# led-cc-driver-mk-2_0.net
KiCad netlist of a schematic drawn in EAGLE
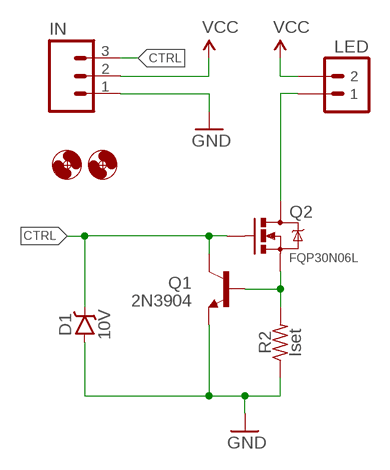
[diagram p0: schematic, sheet 1]

(export (version "E")
  (design (tool "Eeschema 10.0.6"))
  (components
    (comp (ref "D1")
      (value "10V")
      (footprint "eagle-import:DIODE-ZENNER-7.62MM")
      (libsource (lib "eagle-import") (part "DIODE-ZENER7.62MM-PTH"))
    )
    (comp (ref "H1")
      (value "HOLE#2")
      (footprint "eagle-import:HOLE-#2")
      (libsource (lib "eagle-import") (part "HOLE#2"))
    )
    (comp (ref "H2")
      (value "HOLE#2")
      (footprint "eagle-import:HOLE-#2")
      (libsource (lib "eagle-import") (part "HOLE#2"))
    )
    (comp (ref "IN")
      (value "M03PTH")
      (footprint "eagle-import:1X03")
      (libsource (lib "eagle-import") (part "M03PTH"))
    )
    (comp (ref "LED")
      (value "M02PTH")
      (footprint "eagle-import:1X02")
      (libsource (lib "eagle-import") (part "M02PTH"))
    )
    (comp (ref "Q1")
      (value "2N3904")
      (footprint "eagle-import:TO-92-AMMO")
      (libsource (lib "eagle-import") (part "TRANSISTOR_NPNTO-92-AMMO-EBC"))
    )
    (comp (ref "Q2")
      (value "FQP30N06L")
      (footprint "eagle-import:TO220-THERMPAD")
      (libsource (lib "eagle-import") (part "MOSFET-NCHANNELTO-220"))
    )
    (comp (ref "R2")
      (value "Iset")
      (footprint "eagle-import:RESISTOR-AXIAL-PTH-10.16MM")
      (libsource (lib "eagle-import") (part "RESISTORPTH-AXIAL-10.16MM"))
    )
  )
  (nets
    (net (code "1") (name "CTRL") (class "Default")
      (node (ref "D1") (pin "K") (pinfunction "C_K") (pintype "passive"))
      (node (ref "IN") (pin "3") (pinfunction "3_3") (pintype "passive"))
      (node (ref "Q1") (pin "3") (pinfunction "C_3") (pintype "passive"))
      (node (ref "Q2") (pin "1") (pinfunction "G_1") (pintype "passive"))
    )
    (net (code "2") (name "GND") (class "Default")
      (node (ref "D1") (pin "A") (pinfunction "A_A") (pintype "passive"))
      (node (ref "IN") (pin "1") (pinfunction "1_1") (pintype "passive"))
      (node (ref "Q1") (pin "1") (pinfunction "E_1") (pintype "passive"))
      (node (ref "R2") (pin "P$1") (pinfunction "1_P$1") (pintype "passive"))
    )
    (net (code "3") (name "Net-(LED-Pad1)") (class "Default")
      (node (ref "LED") (pin "1") (pinfunction "1_1") (pintype "passive"))
      (node (ref "Q2") (pin "2@1") (pinfunction "D_2@1") (pintype "passive"))
      (node (ref "Q2") (pin "2@2") (pinfunction "D_2@2") (pintype "passive"))
    )
    (net (code "4") (name "Net-(Q1-B)") (class "Default")
      (node (ref "Q1") (pin "2") (pinfunction "B_2") (pintype "passive"))
      (node (ref "Q2") (pin "3") (pinfunction "S_3") (pintype "passive"))
      (node (ref "R2") (pin "P$2") (pinfunction "2_P$2") (pintype "passive"))
    )
    (net (code "5") (name "VCC") (class "Default")
      (node (ref "IN") (pin "2") (pinfunction "2_2") (pintype "passive"))
      (node (ref "LED") (pin "2") (pinfunction "2_2") (pintype "passive"))
    )
  )
)
